# G2Prj.net
KiCad netlist of a schematic drawn in Altium Designer
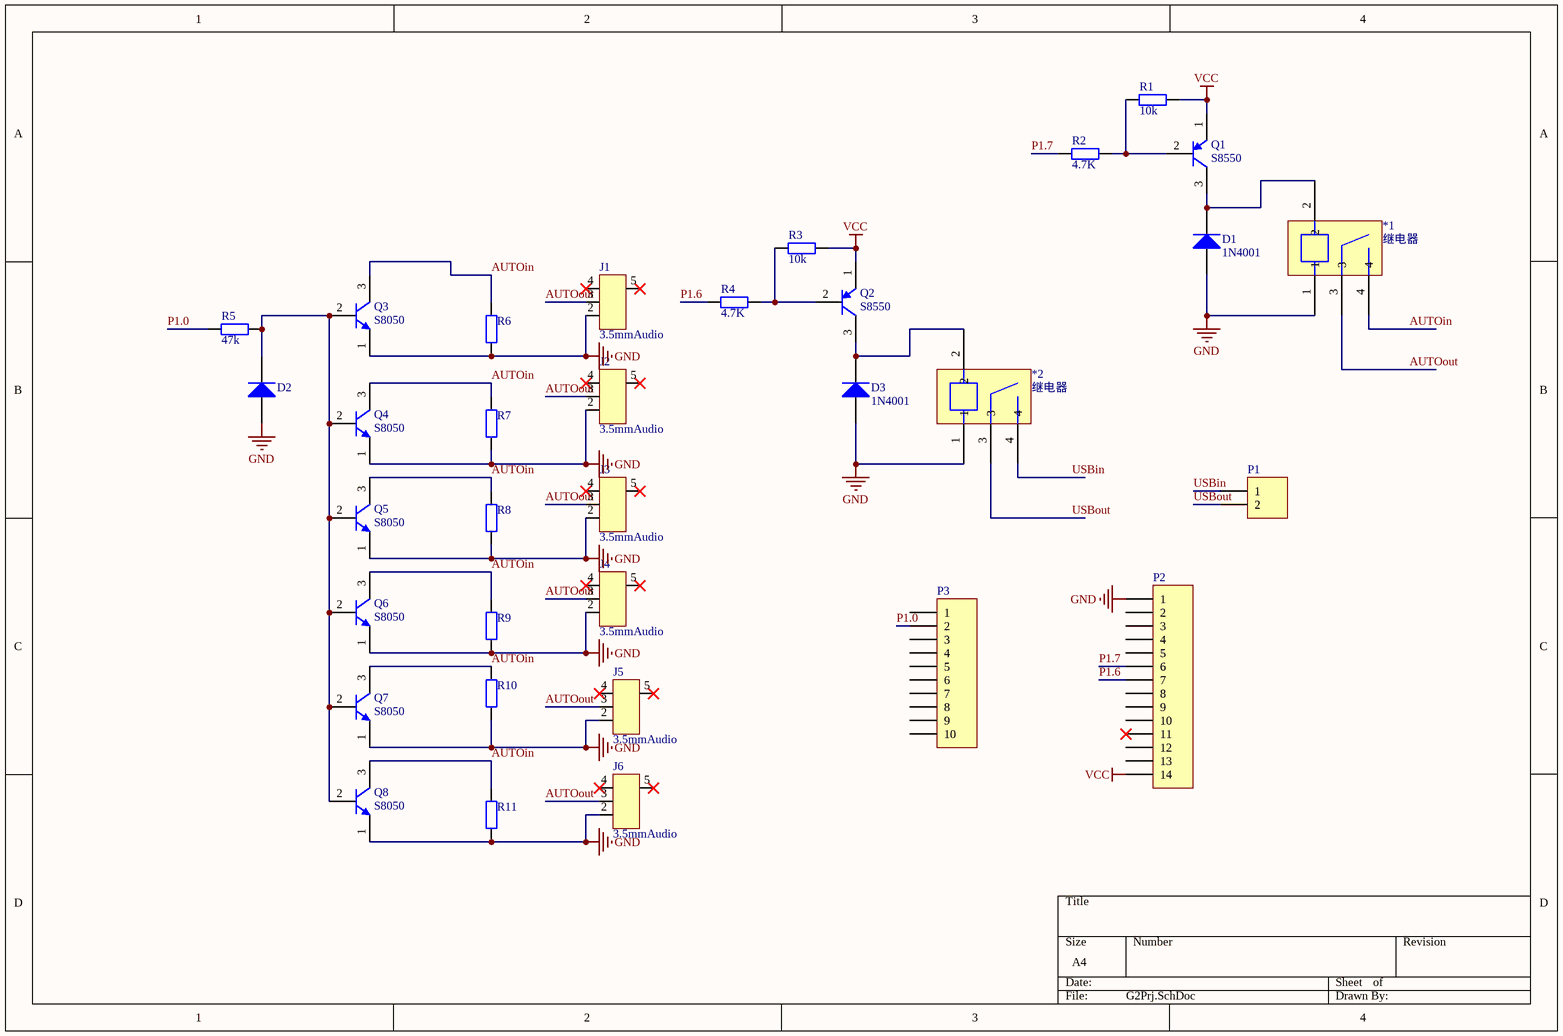
[diagram p0: G2Prj.SchDoc]

(export (version "E")
  (design (tool "Eeschema 10.0.6"))
  (components
    (comp (ref "*1")
      (value "继电器")
      (footprint "PCBComponent_1")
      (libsource (lib "Integrated_Library") (part "Component_1"))
    )
    (comp (ref "*2")
      (value "继电器")
      (footprint "PCBComponent_1")
      (libsource (lib "Integrated_Library") (part "Component_1"))
    )
    (comp (ref "D1")
      (value "Diode")
      (footprint "DIODE-1206")
      (description "二极管")
      (fields (field (name "TYPE") "1N4001") (field (name "PUBLISHER") "Altium Limited"))
      (libsource (lib "常用元器件库_4") (part "Diode"))
    )
    (comp (ref "D2")
      (value "Diode")
      (footprint "DIODE-1206")
      (description "二极管")
      (fields (field (name "PUBLISHER") "Altium Limited"))
      (libsource (lib "常用元器件库_4") (part "Diode"))
    )
    (comp (ref "D3")
      (value "Diode")
      (footprint "DIODE-1206")
      (description "二极管")
      (fields (field (name "TYPE") "1N4001") (field (name "PUBLISHER") "Altium Limited"))
      (libsource (lib "常用元器件库_4") (part "Diode"))
    )
    (comp (ref "J1")
      (value "3.5mmAudio")
      (footprint "Audio")
      (libsource (lib "AudioSwitch") (part "3.5mmAudio"))
    )
    (comp (ref "J2")
      (value "3.5mmAudio")
      (footprint "Audio")
      (libsource (lib "AudioSwitch") (part "3.5mmAudio"))
    )
    (comp (ref "J3")
      (value "3.5mmAudio")
      (footprint "Audio")
      (libsource (lib "AudioSwitch") (part "3.5mmAudio"))
    )
    (comp (ref "J4")
      (value "3.5mmAudio")
      (footprint "Audio")
      (libsource (lib "AudioSwitch") (part "3.5mmAudio"))
    )
    (comp (ref "J5")
      (value "3.5mmAudio")
      (footprint "Audio")
      (libsource (lib "AudioSwitch") (part "3.5mmAudio"))
    )
    (comp (ref "J6")
      (value "3.5mmAudio")
      (footprint "Audio")
      (libsource (lib "AudioSwitch") (part "3.5mmAudio"))
    )
    (comp (ref "P1")
      (value "Header 2")
      (footprint "HDR1X2")
      (description "Header, 2-Pin")
      (fields (field (name "PUBLISHER") "Altium Limited"))
      (libsource (lib "Miscellaneous Connectors") (part "Header 2"))
    )
    (comp (ref "P2")
      (value "Header 14")
      (footprint "HDR1X14")
      (description "Header, 14-Pin")
      (fields (field (name "PUBLISHER") "Altium Limited"))
      (libsource (lib "Miscellaneous Connectors") (part "Header 14"))
    )
    (comp (ref "P3")
      (value "Header 10")
      (footprint "HDR1X10")
      (description "Header, 10-Pin")
      (fields (field (name "PUBLISHER") "Altium Limited"))
      (libsource (lib "Miscellaneous Connectors") (part "Header 10"))
    )
    (comp (ref "Q1")
      (value "S8550")
      (footprint "TO-92A")
      (description "PNP三极管")
      (fields (field (name "PUBLISHER") "Altium Limited"))
      (libsource (lib "常用元器件库_4") (part "S8550"))
    )
    (comp (ref "Q2")
      (value "S8550")
      (footprint "TO-92A")
      (description "PNP三极管")
      (fields (field (name "PUBLISHER") "Altium Limited"))
      (libsource (lib "常用元器件库_4") (part "S8550"))
    )
    (comp (ref "Q3")
      (value "S8050")
      (footprint "TO-92A")
      (description "NPN三极管")
      (fields (field (name "PUBLISHER") "Altium Limited"))
      (libsource (lib "常用元器件库_4") (part "S8050"))
    )
    (comp (ref "Q4")
      (value "S8050")
      (footprint "TO-92A")
      (description "NPN三极管")
      (fields (field (name "PUBLISHER") "Altium Limited"))
      (libsource (lib "常用元器件库_4") (part "S8050"))
    )
    (comp (ref "Q5")
      (value "S8050")
      (footprint "TO-92A")
      (description "NPN三极管")
      (fields (field (name "PUBLISHER") "Altium Limited"))
      (libsource (lib "常用元器件库_4") (part "S8050"))
    )
    (comp (ref "Q6")
      (value "S8050")
      (footprint "TO-92A")
      (description "NPN三极管")
      (fields (field (name "PUBLISHER") "Altium Limited"))
      (libsource (lib "常用元器件库_4") (part "S8050"))
    )
    (comp (ref "Q7")
      (value "S8050")
      (footprint "TO-92A")
      (description "NPN三极管")
      (fields (field (name "PUBLISHER") "Altium Limited"))
      (libsource (lib "常用元器件库_4") (part "S8050"))
    )
    (comp (ref "Q8")
      (value "S8050")
      (footprint "TO-92A")
      (description "NPN三极管")
      (fields (field (name "PUBLISHER") "Altium Limited"))
      (libsource (lib "常用元器件库_4") (part "S8050"))
    )
    (comp (ref "R1")
      (value "10k")
      (footprint "0805")
      (description "Resistor")
      (libsource (lib "") (part "Res_1"))
    )
    (comp (ref "R2")
      (value "4.7K")
      (footprint "0805")
      (description "Resistor")
      (libsource (lib "") (part "Res_1"))
    )
    (comp (ref "R3")
      (value "10k")
      (footprint "0805")
      (description "Resistor")
      (libsource (lib "") (part "Res_1"))
    )
    (comp (ref "R4")
      (value "4.7K")
      (footprint "0805")
      (description "Resistor")
      (libsource (lib "") (part "Res_1"))
    )
    (comp (ref "R5")
      (value "47k")
      (footprint "0805")
      (description "Resistor")
      (libsource (lib "") (part "Res_1"))
    )
    (comp (ref "R6")
      (value "2K")
      (footprint "0805")
      (description "Resistor")
      (libsource (lib "") (part "Res_2"))
    )
    (comp (ref "R7")
      (value "2K")
      (footprint "0805")
      (description "Resistor")
      (libsource (lib "常用元器件库_1") (part "Res"))
    )
    (comp (ref "R8")
      (value "2K")
      (footprint "0805")
      (description "Resistor")
      (libsource (lib "") (part "Res_2"))
    )
    (comp (ref "R9")
      (value "2K")
      (footprint "0805")
      (description "Resistor")
      (libsource (lib "常用元器件库_1") (part "Res"))
    )
    (comp (ref "R10")
      (value "2K")
      (footprint "0805")
      (description "Resistor")
      (libsource (lib "") (part "Res_2"))
    )
    (comp (ref "R11")
      (value "2K")
      (footprint "0805")
      (description "Resistor")
      (libsource (lib "常用元器件库_1") (part "Res"))
    )
  )
  (nets
    (net (code "1") (name "/AUTOin") (class "Default")
      (node (ref "*1") (pin "4") (pinfunction "4_4") (pintype "passive"))
      (node (ref "Q3") (pin "3") (pinfunction "C_3") (pintype "passive"))
      (node (ref "Q4") (pin "3") (pinfunction "C_3") (pintype "passive"))
      (node (ref "Q5") (pin "3") (pinfunction "C_3") (pintype "passive"))
      (node (ref "Q6") (pin "3") (pinfunction "C_3") (pintype "passive"))
      (node (ref "Q7") (pin "3") (pinfunction "C_3") (pintype "passive"))
      (node (ref "Q8") (pin "3") (pinfunction "C_3") (pintype "passive"))
      (node (ref "R10") (pin "2") (pinfunction "2_2") (pintype "passive"))
      (node (ref "R11") (pin "1") (pinfunction "1_1") (pintype "passive"))
      (node (ref "R6") (pin "2") (pinfunction "2_2") (pintype "passive"))
      (node (ref "R7") (pin "1") (pinfunction "1_1") (pintype "passive"))
      (node (ref "R8") (pin "2") (pinfunction "2_2") (pintype "passive"))
      (node (ref "R9") (pin "1") (pinfunction "1_1") (pintype "passive"))
    )
    (net (code "2") (name "/AUTOout") (class "Default")
      (node (ref "*1") (pin "3") (pinfunction "3_3") (pintype "passive"))
      (node (ref "J1") (pin "3") (pinfunction "20_3") (pintype "passive"))
      (node (ref "J2") (pin "3") (pinfunction "20_3") (pintype "passive"))
      (node (ref "J3") (pin "3") (pinfunction "20_3") (pintype "passive"))
      (node (ref "J4") (pin "3") (pinfunction "20_3") (pintype "passive"))
      (node (ref "J5") (pin "3") (pinfunction "20_3") (pintype "passive"))
      (node (ref "J6") (pin "3") (pinfunction "20_3") (pintype "passive"))
    )
    (net (code "3") (name "/P1.0") (class "Default")
      (node (ref "P3") (pin "2") (pinfunction "2_2") (pintype "passive"))
      (node (ref "R5") (pin "1") (pinfunction "1_1") (pintype "passive"))
    )
    (net (code "4") (name "/P1.6") (class "Default")
      (node (ref "P2") (pin "7") (pinfunction "7_7") (pintype "passive"))
      (node (ref "R4") (pin "1") (pinfunction "1_1") (pintype "passive"))
    )
    (net (code "5") (name "/P1.7") (class "Default")
      (node (ref "P2") (pin "6") (pinfunction "6_6") (pintype "passive"))
      (node (ref "R2") (pin "1") (pinfunction "1_1") (pintype "passive"))
    )
    (net (code "6") (name "/USBin") (class "Default")
      (node (ref "*2") (pin "4") (pinfunction "4_4") (pintype "passive"))
      (node (ref "P1") (pin "1") (pinfunction "1_1") (pintype "passive"))
    )
    (net (code "7") (name "/USBout") (class "Default")
      (node (ref "*2") (pin "3") (pinfunction "3_3") (pintype "passive"))
      (node (ref "P1") (pin "2") (pinfunction "2_2") (pintype "passive"))
    )
    (net (code "8") (name "GND") (class "Default")
      (node (ref "*1") (pin "1") (pinfunction "1_1") (pintype "passive"))
      (node (ref "*2") (pin "1") (pinfunction "1_1") (pintype "passive"))
      (node (ref "D1") (pin "1") (pinfunction "A_1") (pintype "passive"))
      (node (ref "D2") (pin "1") (pinfunction "A_1") (pintype "passive"))
      (node (ref "D3") (pin "1") (pinfunction "A_1") (pintype "passive"))
      (node (ref "J1") (pin "2") (pinfunction "19_2") (pintype "passive"))
      (node (ref "J2") (pin "2") (pinfunction "19_2") (pintype "passive"))
      (node (ref "J3") (pin "2") (pinfunction "19_2") (pintype "passive"))
      (node (ref "J4") (pin "2") (pinfunction "19_2") (pintype "passive"))
      (node (ref "J5") (pin "2") (pinfunction "19_2") (pintype "passive"))
      (node (ref "J6") (pin "2") (pinfunction "19_2") (pintype "passive"))
      (node (ref "P2") (pin "1") (pinfunction "1_1") (pintype "passive"))
      (node (ref "Q3") (pin "1") (pinfunction "E_1") (pintype "passive"))
      (node (ref "Q4") (pin "1") (pinfunction "E_1") (pintype "passive"))
      (node (ref "Q5") (pin "1") (pinfunction "E_1") (pintype "passive"))
      (node (ref "Q6") (pin "1") (pinfunction "E_1") (pintype "passive"))
      (node (ref "Q7") (pin "1") (pinfunction "E_1") (pintype "passive"))
      (node (ref "Q8") (pin "1") (pinfunction "E_1") (pintype "passive"))
      (node (ref "R10") (pin "1") (pinfunction "1_1") (pintype "passive"))
      (node (ref "R11") (pin "2") (pinfunction "2_2") (pintype "passive"))
      (node (ref "R6") (pin "1") (pinfunction "1_1") (pintype "passive"))
      (node (ref "R7") (pin "2") (pinfunction "2_2") (pintype "passive"))
      (node (ref "R8") (pin "1") (pinfunction "1_1") (pintype "passive"))
      (node (ref "R9") (pin "2") (pinfunction "2_2") (pintype "passive"))
    )
    (net (code "9") (name "Net-(D1-K)") (class "Default")
      (node (ref "*1") (pin "2") (pinfunction "2_2") (pintype "passive"))
      (node (ref "D1") (pin "2") (pinfunction "K_2") (pintype "passive"))
      (node (ref "Q1") (pin "3") (pinfunction "C_3") (pintype "passive"))
    )
    (net (code "10") (name "Net-(D2-K)") (class "Default")
      (node (ref "D2") (pin "2") (pinfunction "K_2") (pintype "passive"))
      (node (ref "Q3") (pin "2") (pinfunction "B_2") (pintype "passive"))
      (node (ref "Q4") (pin "2") (pinfunction "B_2") (pintype "passive"))
      (node (ref "Q5") (pin "2") (pinfunction "B_2") (pintype "passive"))
      (node (ref "Q6") (pin "2") (pinfunction "B_2") (pintype "passive"))
      (node (ref "Q7") (pin "2") (pinfunction "B_2") (pintype "passive"))
      (node (ref "Q8") (pin "2") (pinfunction "B_2") (pintype "passive"))
      (node (ref "R5") (pin "2") (pinfunction "2_2") (pintype "passive"))
    )
    (net (code "11") (name "Net-(D3-K)") (class "Default")
      (node (ref "*2") (pin "2") (pinfunction "2_2") (pintype "passive"))
      (node (ref "D3") (pin "2") (pinfunction "K_2") (pintype "passive"))
      (node (ref "Q2") (pin "3") (pinfunction "C_3") (pintype "passive"))
    )
    (net (code "12") (name "Net-(Q1-B)") (class "Default")
      (node (ref "Q1") (pin "2") (pinfunction "B_2") (pintype "passive"))
      (node (ref "R1") (pin "1") (pinfunction "1_1") (pintype "passive"))
      (node (ref "R2") (pin "2") (pinfunction "2_2") (pintype "passive"))
    )
    (net (code "13") (name "Net-(Q2-B)") (class "Default")
      (node (ref "Q2") (pin "2") (pinfunction "B_2") (pintype "passive"))
      (node (ref "R3") (pin "1") (pinfunction "1_1") (pintype "passive"))
      (node (ref "R4") (pin "2") (pinfunction "2_2") (pintype "passive"))
    )
    (net (code "14") (name "VCC") (class "Default")
      (node (ref "P2") (pin "14") (pinfunction "14_14") (pintype "passive"))
      (node (ref "Q1") (pin "1") (pinfunction "E_1") (pintype "passive"))
      (node (ref "Q2") (pin "1") (pinfunction "E_1") (pintype "passive"))
      (node (ref "R1") (pin "2") (pinfunction "2_2") (pintype "passive"))
      (node (ref "R3") (pin "2") (pinfunction "2_2") (pintype "passive"))
    )
    (net (code "15") (name "unconnected-(J1-21-Pad4)") (class "Default")
      (node (ref "J1") (pin "4") (pinfunction "21_4") (pintype "passive+no_connect"))
    )
    (net (code "16") (name "unconnected-(J1-22-Pad5)") (class "Default")
      (node (ref "J1") (pin "5") (pinfunction "22_5") (pintype "passive+no_connect"))
    )
    (net (code "17") (name "unconnected-(J2-21-Pad4)") (class "Default")
      (node (ref "J2") (pin "4") (pinfunction "21_4") (pintype "passive+no_connect"))
    )
    (net (code "18") (name "unconnected-(J2-22-Pad5)") (class "Default")
      (node (ref "J2") (pin "5") (pinfunction "22_5") (pintype "passive+no_connect"))
    )
    (net (code "19") (name "unconnected-(J3-21-Pad4)") (class "Default")
      (node (ref "J3") (pin "4") (pinfunction "21_4") (pintype "passive+no_connect"))
    )
    (net (code "20") (name "unconnected-(J3-22-Pad5)") (class "Default")
      (node (ref "J3") (pin "5") (pinfunction "22_5") (pintype "passive+no_connect"))
    )
    (net (code "21") (name "unconnected-(J4-21-Pad4)") (class "Default")
      (node (ref "J4") (pin "4") (pinfunction "21_4") (pintype "passive+no_connect"))
    )
    (net (code "22") (name "unconnected-(J4-22-Pad5)") (class "Default")
      (node (ref "J4") (pin "5") (pinfunction "22_5") (pintype "passive+no_connect"))
    )
    (net (code "23") (name "unconnected-(J5-21-Pad4)") (class "Default")
      (node (ref "J5") (pin "4") (pinfunction "21_4") (pintype "passive+no_connect"))
    )
    (net (code "24") (name "unconnected-(J5-22-Pad5)") (class "Default")
      (node (ref "J5") (pin "5") (pinfunction "22_5") (pintype "passive+no_connect"))
    )
    (net (code "25") (name "unconnected-(J6-21-Pad4)") (class "Default")
      (node (ref "J6") (pin "4") (pinfunction "21_4") (pintype "passive+no_connect"))
    )
    (net (code "26") (name "unconnected-(J6-22-Pad5)") (class "Default")
      (node (ref "J6") (pin "5") (pinfunction "22_5") (pintype "passive+no_connect"))
    )
    (net (code "27") (name "unconnected-(P2-Pad2)") (class "Default")
      (node (ref "P2") (pin "2") (pinfunction "2_2") (pintype "passive"))
    )
    (net (code "28") (name "unconnected-(P2-Pad3)") (class "Default")
      (node (ref "P2") (pin "3") (pinfunction "3_3") (pintype "passive"))
    )
    (net (code "29") (name "unconnected-(P2-Pad4)") (class "Default")
      (node (ref "P2") (pin "4") (pinfunction "4_4") (pintype "passive"))
    )
    (net (code "30") (name "unconnected-(P2-Pad5)") (class "Default")
      (node (ref "P2") (pin "5") (pinfunction "5_5") (pintype "passive"))
    )
    (net (code "31") (name "unconnected-(P2-Pad8)") (class "Default")
      (node (ref "P2") (pin "8") (pinfunction "8_8") (pintype "passive"))
    )
    (net (code "32") (name "unconnected-(P2-Pad9)") (class "Default")
      (node (ref "P2") (pin "9") (pinfunction "9_9") (pintype "passive"))
    )
    (net (code "33") (name "unconnected-(P2-Pad10)") (class "Default")
      (node (ref "P2") (pin "10") (pinfunction "10_10") (pintype "passive"))
    )
    (net (code "34") (name "unconnected-(P2-Pad11)") (class "Default")
      (node (ref "P2") (pin "11") (pinfunction "11_11") (pintype "passive+no_connect"))
    )
    (net (code "35") (name "unconnected-(P2-Pad12)") (class "Default")
      (node (ref "P2") (pin "12") (pinfunction "12_12") (pintype "passive"))
    )
    (net (code "36") (name "unconnected-(P2-Pad13)") (class "Default")
      (node (ref "P2") (pin "13") (pinfunction "13_13") (pintype "passive"))
    )
    (net (code "37") (name "unconnected-(P3-Pad1)") (class "Default")
      (node (ref "P3") (pin "1") (pinfunction "1_1") (pintype "passive"))
    )
    (net (code "38") (name "unconnected-(P3-Pad3)") (class "Default")
      (node (ref "P3") (pin "3") (pinfunction "3_3") (pintype "passive"))
    )
    (net (code "39") (name "unconnected-(P3-Pad4)") (class "Default")
      (node (ref "P3") (pin "4") (pinfunction "4_4") (pintype "passive"))
    )
    (net (code "40") (name "unconnected-(P3-Pad5)") (class "Default")
      (node (ref "P3") (pin "5") (pinfunction "5_5") (pintype "passive"))
    )
    (net (code "41") (name "unconnected-(P3-Pad6)") (class "Default")
      (node (ref "P3") (pin "6") (pinfunction "6_6") (pintype "passive"))
    )
    (net (code "42") (name "unconnected-(P3-Pad7)") (class "Default")
      (node (ref "P3") (pin "7") (pinfunction "7_7") (pintype "passive"))
    )
    (net (code "43") (name "unconnected-(P3-Pad8)") (class "Default")
      (node (ref "P3") (pin "8") (pinfunction "8_8") (pintype "passive"))
    )
    (net (code "44") (name "unconnected-(P3-Pad9)") (class "Default")
      (node (ref "P3") (pin "9") (pinfunction "9_9") (pintype "passive"))
    )
    (net (code "45") (name "unconnected-(P3-Pad10)") (class "Default")
      (node (ref "P3") (pin "10") (pinfunction "10_10") (pintype "passive"))
    )
  )
)
